# TXdispatcherBoard.net
KiCad netlist of a schematic drawn in Altium Designer
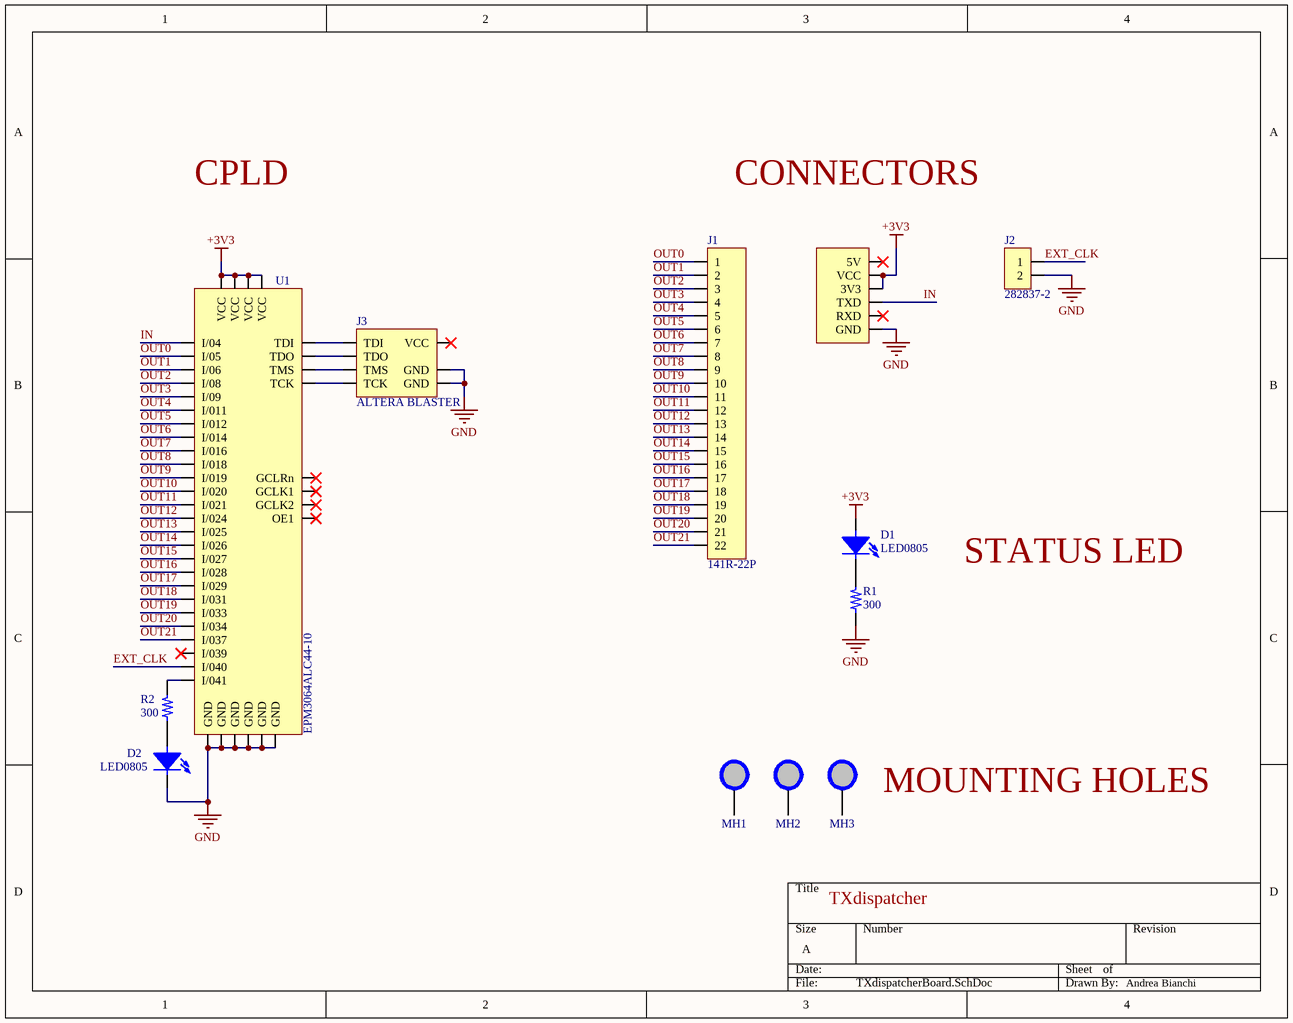
[diagram p0: TXdispatcherBoard.SchDoc]

(export (version "E")
  (design (tool "Eeschema 10.0.6"))
  (components
    (comp (ref "D1")
      (value "LED0805")
      (footprint "LED0805")
      (description "LED0805 any color")
      (libsource (lib "TXdispatcherBoard") (part "LED0805"))
    )
    (comp (ref "D2")
      (value "LED0805")
      (footprint "LED0805")
      (description "LED0805 any color")
      (libsource (lib "TXdispatcherBoard") (part "LED0805"))
    )
    (comp (ref "J1")
      (value "141R-22P")
      (footprint "141R-22P")
      (libsource (lib "TXdispatcherBoard") (part "141R-22P"))
    )
    (comp (ref "J2")
      (value "282837-2")
      (footprint "282837-2")
      (description "Conn Terminal Blocks F 2 POS 5.08mm Solder ST Thru-Hole 13.5A/Contact")
      (fields (field (name "MANUFACTURER") "TE Connectivity") (field (name "VOLTAGE") "300V"))
      (libsource (lib "TXdispatcherBoard") (part "282837-2"))
    )
    (comp (ref "J3")
      (value "ALTERA BLASTER")
      (footprint "ALTERA_BLASTER")
      (libsource (lib "TXdispatcherBoard") (part "ALTERA_JTAG"))
    )
    (comp (ref "J4")
      (value "USB_FTDI_CONVERTER")
      (footprint "usb_ftdi")
      (libsource (lib "TXdispatcherBoard") (part "USB_FTDI_CONVERTER"))
    )
    (comp (ref "MH1")
      (value "MH 3.2mm NP")
      (footprint "MH3.0mm")
      (description "Mounting hole 3.2mm non plated")
      (libsource (lib "TXdispatcherBoard") (part "MHNP"))
    )
    (comp (ref "MH2")
      (value "MH 3.2mm NP")
      (footprint "MH3.0mm")
      (description "Mounting hole 3.2mm non plated")
      (libsource (lib "TXdispatcherBoard") (part "MHNP"))
    )
    (comp (ref "MH3")
      (value "MH 3.2mm NP")
      (footprint "MH3.0mm")
      (description "Mounting hole 3.2mm non plated")
      (libsource (lib "TXdispatcherBoard") (part "MHNP"))
    )
    (comp (ref "R1") (value "300") (footprint "R0805") (libsource (lib "TXdispatcherBoard") (part "R0805")))
    (comp (ref "R2") (value "300") (footprint "R0805") (libsource (lib "TXdispatcherBoard") (part "R0805")))
    (comp (ref "U1")
      (value "EPM3064ALC44-10")
      (footprint "PLCC44_DIP")
      (description "IC CPLD 64MC 10NS 44PLCC")
      (fields (field (name "MANUFACTURER") "Intel Altera"))
      (libsource (lib "TXdispatcherBoard") (part "EPM3064ALC44-10"))
    )
  )
  (nets
    (net (code "1") (name "+3V3") (class "Default")
      (node (ref "D1") (pin "2") (pinfunction "A_2") (pintype "passive"))
      (node (ref "J4") (pin "2") (pinfunction "VCC_2") (pintype "passive"))
      (node (ref "J4") (pin "3") (pinfunction "3V3_3") (pintype "passive"))
      (node (ref "U1") (pin "15") (pinfunction "VCC_15") (pintype "passive"))
      (node (ref "U1") (pin "23") (pinfunction "VCC_23") (pintype "passive"))
      (node (ref "U1") (pin "3") (pinfunction "VCC_3") (pintype "passive"))
      (node (ref "U1") (pin "35") (pinfunction "VCC_35") (pintype "passive"))
    )
    (net (code "2") (name "/EXT_CLK") (class "Default")
      (node (ref "J2") (pin "1") (pinfunction "1_1") (pintype "passive"))
      (node (ref "U1") (pin "40") (pinfunction "I/040_40") (pintype "passive"))
    )
    (net (code "3") (name "/IN") (class "Default")
      (node (ref "J4") (pin "4") (pinfunction "TXD_4") (pintype "passive"))
      (node (ref "U1") (pin "4") (pinfunction "I/04_4") (pintype "passive"))
    )
    (net (code "4") (name "/OUT0") (class "Default")
      (node (ref "J1") (pin "1") (pinfunction "1_1") (pintype "passive"))
      (node (ref "U1") (pin "5") (pinfunction "I/05_5") (pintype "passive"))
    )
    (net (code "5") (name "/OUT1") (class "Default")
      (node (ref "J1") (pin "2") (pinfunction "2_2") (pintype "passive"))
      (node (ref "U1") (pin "6") (pinfunction "I/06_6") (pintype "passive"))
    )
    (net (code "6") (name "/OUT2") (class "Default")
      (node (ref "J1") (pin "3") (pinfunction "3_3") (pintype "passive"))
      (node (ref "U1") (pin "8") (pinfunction "I/08_8") (pintype "passive"))
    )
    (net (code "7") (name "/OUT3") (class "Default")
      (node (ref "J1") (pin "4") (pinfunction "4_4") (pintype "passive"))
      (node (ref "U1") (pin "9") (pinfunction "I/09_9") (pintype "passive"))
    )
    (net (code "8") (name "/OUT4") (class "Default")
      (node (ref "J1") (pin "5") (pinfunction "5_5") (pintype "passive"))
      (node (ref "U1") (pin "11") (pinfunction "I/011_11") (pintype "passive"))
    )
    (net (code "9") (name "/OUT5") (class "Default")
      (node (ref "J1") (pin "6") (pinfunction "6_6") (pintype "passive"))
      (node (ref "U1") (pin "12") (pinfunction "I/012_12") (pintype "passive"))
    )
    (net (code "10") (name "/OUT6") (class "Default")
      (node (ref "J1") (pin "7") (pinfunction "7_7") (pintype "passive"))
      (node (ref "U1") (pin "14") (pinfunction "I/014_14") (pintype "passive"))
    )
    (net (code "11") (name "/OUT7") (class "Default")
      (node (ref "J1") (pin "8") (pinfunction "8_8") (pintype "passive"))
      (node (ref "U1") (pin "16") (pinfunction "I/016_16") (pintype "passive"))
    )
    (net (code "12") (name "/OUT8") (class "Default")
      (node (ref "J1") (pin "9") (pinfunction "9_9") (pintype "passive"))
      (node (ref "U1") (pin "18") (pinfunction "I/018_18") (pintype "passive"))
    )
    (net (code "13") (name "/OUT9") (class "Default")
      (node (ref "J1") (pin "10") (pinfunction "10_10") (pintype "passive"))
      (node (ref "U1") (pin "19") (pinfunction "I/019_19") (pintype "passive"))
    )
    (net (code "14") (name "/OUT10") (class "Default")
      (node (ref "J1") (pin "11") (pinfunction "11_11") (pintype "passive"))
      (node (ref "U1") (pin "20") (pinfunction "I/020_20") (pintype "passive"))
    )
    (net (code "15") (name "/OUT11") (class "Default")
      (node (ref "J1") (pin "12") (pinfunction "12_12") (pintype "passive"))
      (node (ref "U1") (pin "21") (pinfunction "I/021_21") (pintype "passive"))
    )
    (net (code "16") (name "/OUT12") (class "Default")
      (node (ref "J1") (pin "13") (pinfunction "13_13") (pintype "passive"))
      (node (ref "U1") (pin "24") (pinfunction "I/024_24") (pintype "passive"))
    )
    (net (code "17") (name "/OUT13") (class "Default")
      (node (ref "J1") (pin "14") (pinfunction "14_14") (pintype "passive"))
      (node (ref "U1") (pin "25") (pinfunction "I/025_25") (pintype "passive"))
    )
    (net (code "18") (name "/OUT14") (class "Default")
      (node (ref "J1") (pin "15") (pinfunction "15_15") (pintype "passive"))
      (node (ref "U1") (pin "26") (pinfunction "I/026_26") (pintype "passive"))
    )
    (net (code "19") (name "/OUT15") (class "Default")
      (node (ref "J1") (pin "16") (pinfunction "16_16") (pintype "passive"))
      (node (ref "U1") (pin "27") (pinfunction "I/027_27") (pintype "passive"))
    )
    (net (code "20") (name "/OUT16") (class "Default")
      (node (ref "J1") (pin "17") (pinfunction "17_17") (pintype "passive"))
      (node (ref "U1") (pin "28") (pinfunction "I/028_28") (pintype "passive"))
    )
    (net (code "21") (name "/OUT17") (class "Default")
      (node (ref "J1") (pin "18") (pinfunction "18_18") (pintype "passive"))
      (node (ref "U1") (pin "29") (pinfunction "I/029_29") (pintype "passive"))
    )
    (net (code "22") (name "/OUT18") (class "Default")
      (node (ref "J1") (pin "19") (pinfunction "19_19") (pintype "passive"))
      (node (ref "U1") (pin "31") (pinfunction "I/031_31") (pintype "passive"))
    )
    (net (code "23") (name "/OUT19") (class "Default")
      (node (ref "J1") (pin "20") (pinfunction "20_20") (pintype "passive"))
      (node (ref "U1") (pin "33") (pinfunction "I/033_33") (pintype "passive"))
    )
    (net (code "24") (name "/OUT20") (class "Default")
      (node (ref "J1") (pin "21") (pinfunction "21_21") (pintype "passive"))
      (node (ref "U1") (pin "34") (pinfunction "I/034_34") (pintype "passive"))
    )
    (net (code "25") (name "/OUT21") (class "Default")
      (node (ref "J1") (pin "22") (pinfunction "22_22") (pintype "passive"))
      (node (ref "U1") (pin "37") (pinfunction "I/037_37") (pintype "passive"))
    )
    (net (code "26") (name "GND") (class "Default")
      (node (ref "D2") (pin "1") (pinfunction "C_1") (pintype "passive"))
      (node (ref "J2") (pin "2") (pinfunction "2_2") (pintype "passive"))
      (node (ref "J3") (pin "10") (pinfunction "GND_10") (pintype "passive"))
      (node (ref "J3") (pin "2") (pinfunction "GND_2") (pintype "passive"))
      (node (ref "J4") (pin "6") (pinfunction "GND_6") (pintype "passive"))
      (node (ref "R1") (pin "1") (pinfunction "1_1") (pintype "passive"))
      (node (ref "U1") (pin "10") (pinfunction "GND_10") (pintype "passive"))
      (node (ref "U1") (pin "17") (pinfunction "GND_17") (pintype "passive"))
      (node (ref "U1") (pin "22") (pinfunction "GND_22") (pintype "passive"))
      (node (ref "U1") (pin "30") (pinfunction "GND_30") (pintype "passive"))
      (node (ref "U1") (pin "36") (pinfunction "GND_36") (pintype "passive"))
      (node (ref "U1") (pin "42") (pinfunction "GND_42") (pintype "passive"))
    )
    (net (code "27") (name "Net-(D1-C)") (class "Default")
      (node (ref "D1") (pin "1") (pinfunction "C_1") (pintype "passive"))
      (node (ref "R1") (pin "2") (pinfunction "2_2") (pintype "passive"))
    )
    (net (code "28") (name "Net-(D2-A)") (class "Default")
      (node (ref "D2") (pin "2") (pinfunction "A_2") (pintype "passive"))
      (node (ref "R2") (pin "1") (pinfunction "1_1") (pintype "passive"))
    )
    (net (code "29") (name "Net-(J3-TCK)") (class "Default")
      (node (ref "J3") (pin "1") (pinfunction "TCK_1") (pintype "passive"))
      (node (ref "U1") (pin "32") (pinfunction "TCK_32") (pintype "passive"))
    )
    (net (code "30") (name "Net-(J3-TDI)") (class "Default")
      (node (ref "J3") (pin "9") (pinfunction "TDI_9") (pintype "passive"))
      (node (ref "U1") (pin "7") (pinfunction "TDI_7") (pintype "passive"))
    )
    (net (code "31") (name "Net-(J3-TDO)") (class "Default")
      (node (ref "J3") (pin "3") (pinfunction "TDO_3") (pintype "passive"))
      (node (ref "U1") (pin "38") (pinfunction "TDO_38") (pintype "passive"))
    )
    (net (code "32") (name "Net-(J3-TMS)") (class "Default")
      (node (ref "J3") (pin "5") (pinfunction "TMS_5") (pintype "passive"))
      (node (ref "U1") (pin "13") (pinfunction "TMS_13") (pintype "passive"))
    )
    (net (code "33") (name "Net-(U1-I{slash}041)") (class "Default")
      (node (ref "R2") (pin "2") (pinfunction "2_2") (pintype "passive"))
      (node (ref "U1") (pin "41") (pinfunction "I/041_41") (pintype "passive"))
    )
    (net (code "34") (name "unconnected-(J3-VCC-Pad4)") (class "Default")
      (node (ref "J3") (pin "4") (pinfunction "VCC_4") (pintype "passive+no_connect"))
    )
    (net (code "35") (name "unconnected-(J4-5V-Pad1)") (class "Default")
      (node (ref "J4") (pin "1") (pinfunction "5V_1") (pintype "passive+no_connect"))
    )
    (net (code "36") (name "unconnected-(J4-RXD-Pad5)") (class "Default")
      (node (ref "J4") (pin "5") (pinfunction "RXD_5") (pintype "passive+no_connect"))
    )
    (net (code "37") (name "unconnected-(MH1-Pad1)") (class "Default")
      (node (ref "MH1") (pin "1") (pinfunction "1_1") (pintype "passive"))
    )
    (net (code "38") (name "unconnected-(MH2-Pad1)") (class "Default")
      (node (ref "MH2") (pin "1") (pinfunction "1_1") (pintype "passive"))
    )
    (net (code "39") (name "unconnected-(MH3-Pad1)") (class "Default")
      (node (ref "MH3") (pin "1") (pinfunction "1_1") (pintype "passive"))
    )
    (net (code "40") (name "unconnected-(U1-GCLK1-Pad43)") (class "Default")
      (node (ref "U1") (pin "43") (pinfunction "GCLK1_43") (pintype "passive+no_connect"))
    )
    (net (code "41") (name "unconnected-(U1-GCLK2-Pad2)") (class "Default")
      (node (ref "U1") (pin "2") (pinfunction "GCLK2_2") (pintype "passive+no_connect"))
    )
    (net (code "42") (name "unconnected-(U1-GCLRn-Pad1)") (class "Default")
      (node (ref "U1") (pin "1") (pinfunction "GCLRn_1") (pintype "passive+no_connect"))
    )
    (net (code "43") (name "unconnected-(U1-I{slash}039-Pad39)") (class "Default")
      (node (ref "U1") (pin "39") (pinfunction "I/039_39") (pintype "passive+no_connect"))
    )
    (net (code "44") (name "unconnected-(U1-OE1-Pad44)") (class "Default")
      (node (ref "U1") (pin "44") (pinfunction "OE1_44") (pintype "passive+no_connect"))
    )
  )
)
